# USB-C_Serial_16U2.net
KiCad netlist of a schematic drawn in Altium Designer
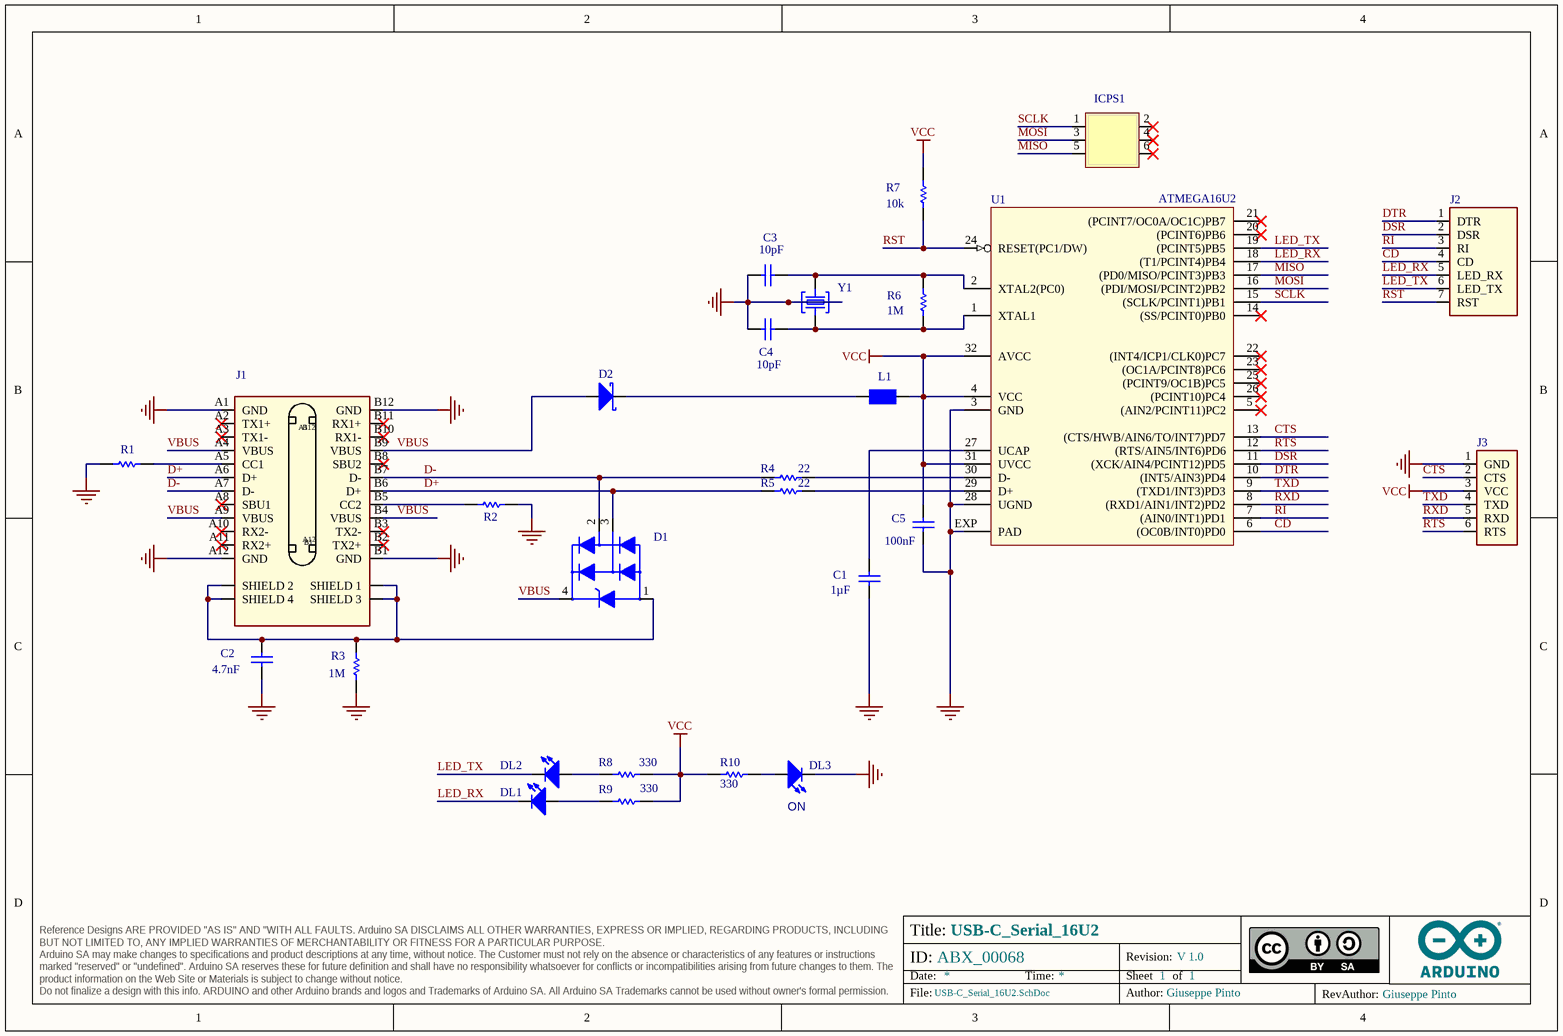
[diagram p0: USB-C_Serial_16U2.SchDoc]

(export (version "E")
  (design (tool "Eeschema 10.0.6"))
  (components
    (comp (ref "C1")
      (value "1µF")
      (footprint "CAP-0402")
      (description "CAP CHIP 0402 1uF 10V X5R 10%")
      (fields (field (name "VOLTAGE") "10V") (field (name "MANUFACTURER") "KEMET"))
      (libsource (lib "Clean") (part "CAP"))
    )
    (comp (ref "C2")
      (value "4.7nF")
      (footprint "CAP-0805")
      (description "CAP CHIP 0805 4.7nF 1000V X7R 10%")
      (fields (field (name "MANUFACTURER") "KEMET") (field (name "VOLTAGE") "1kV"))
      (libsource (lib "Clean") (part "CAP"))
    )
    (comp (ref "C3")
      (value "10pF")
      (footprint "CAP-0402")
      (description "CAP CHIP 0402 10pF 50V C0G 5%")
      (fields (field (name "MANUFACTURER") "KEMET") (field (name "PART NUMBER") "C0402H100J5GACTU"))
      (libsource (lib "Clean") (part "CAP"))
    )
    (comp (ref "C4")
      (value "10pF")
      (footprint "CAP-0402")
      (description "CAP CHIP 0402 10pF 50V C0G 5%")
      (fields (field (name "MANUFACTURER") "KEMET") (field (name "PART NUMBER") "C0402H100J5GACTU"))
      (libsource (lib "Clean") (part "CAP"))
    )
    (comp (ref "C5")
      (value "100nF")
      (footprint "CAP-0402")
      (description "CAP CHIP 0402 100nF 16V X7R 10%")
      (fields (field (name "VOLTAGE") "16V") (field (name "PART NUMBER") "C0402C104K4RACTU"))
      (libsource (lib "Clean") (part "C315C220J2G5TA"))
    )
    (comp (ref "D1")
      (value "PRTR5V0U2X,215")
      (footprint "SOT190P230X110-4N")
      (description "TVS ARRAY 4LIN.8kV 1pF SOT143B")
      (fields (field (name "MANUFACTURER") "Nexperia"))
      (libsource (lib "Clean") (part "PRTR5V0U2X,215"))
    )
    (comp (ref "D2")
      (value "PMEG6020AELRX")
      (footprint "SOD123-1")
      (description "DIODE SCHOTTKY SMD 2A 60V SOD123FL")
      (fields (field (name "MANUFACTURER") "Nexperia"))
      (libsource (lib "Clean") (part "PMEG6020AELRX"))
    )
    (comp (ref "DL1")
      (value "HSMD-C190")
      (footprint "LEDC1608X80N-AK")
      (description "LED SMD 0603 ORANGE604 8mcd DIFF.")
      (fields (field (name "MANUFACTURER") "Broadcom"))
      (libsource (lib "Clean") (part "LED"))
    )
    (comp (ref "DL2")
      (value "HSMD-C190")
      (footprint "LEDC1608X80N-AK")
      (description "LED SMD 0603 ORANGE604 8mcd DIFF.")
      (fields (field (name "MANUFACTURER") "Broadcom"))
      (libsource (lib "Clean") (part "LED"))
    )
    (comp (ref "DL3")
      (value "HSMG-C190")
      (footprint "LEDC1608X80N-AK")
      (description "LED SMD 0603 GREEN/568 15mcd 120^")
      (fields (field (name "MANUFACTURER") "Broadcom"))
      (libsource (lib "Clean") (part "LED"))
    )
    (comp (ref "ICPS1")
      (value "PINHD-2X03-SM-TP")
      (footprint "2X03-TP")
      (description "2X03 6 TEST POINTS")
      (libsource (lib "Clean") (part "Symbol"))
    )
    (comp (ref "J1")
      (value "12401598E4#2A")
      (footprint "12401598E4#2A")
      (description "CONN RCP USB3.1 TYPEC 24P SMD RA")
      (fields (field (name "MANUFACTURER") "Amphenol ICC (Commercial Products)"))
      (libsource (lib "Clean") (part "12401598E4#2A"))
    )
    (comp (ref "J2")
      (value "PH1-07-UA")
      (footprint "CONN STRIP 2.54 PIN HEADER DIP 180° 1x 7 PIN GOLD FLASH castelleted")
      (description "CONN STRIP 2.54 PIN HEADER DIP 180° 1x 7 PIN GOLD FLASH castelleted")
      (fields (field (name "MANUFACTURER") "4 UCONN"))
      (libsource (lib "Clean") (part "PH1-07-UA"))
    )
    (comp (ref "J3")
      (value "PH1-06-UA")
      (footprint "CONN STRP 2.54 PIN HEADER DIP 180° 1x X PIN GOLD FLASH")
      (description "CONN STRP 2.54 PIN HEADER DIP 180° 1x6 PIN GOLD FLASH castellated")
      (fields (field (name "MANUFACTURER") "4UCONN"))
      (libsource (lib "Clean") (part "PH1-06-UA"))
    )
    (comp (ref "L1")
      (value "BLM18PG471SN1D")
      (footprint "L-0603")
      (description "FERRITE SMD 0603 470R 1A 0.2R")
      (fields (field (name "TOLERANCE") "25%") (field (name "MANUFACTURER") "Murata"))
      (libsource (lib "Clean") (part "Ferrite"))
    )
    (comp (ref "R1")
      (value "RC0402FR-075K1L")
      (footprint "RES-0402")
      (description "RES CHIP 0402 5K1 1% 1/16W")
      (fields (field (name "TOLERANCE") "1%") (field (name "MANUFACTURER") "YAGEO"))
      (libsource (lib "Clean") (part "CRCW04025K10FKED"))
    )
    (comp (ref "R2")
      (value "RC0402FR-075K1L")
      (footprint "RES-0402")
      (description "RES CHIP 0402 5K1 1% 1/16W")
      (fields (field (name "TOLERANCE") "1%") (field (name "MANUFACTURER") "YAGEO"))
      (libsource (lib "Clean") (part "CRCW04025K10FKED"))
    )
    (comp (ref "R3")
      (value "1M")
      (footprint "RES-0402")
      (description "RES CHIP 0402 1M 1% 1/16W")
      (fields (field (name "POWER") "63mW") (field (name "TOLERANCE") "1%"))
      (libsource (lib "Clean") (part "RES"))
    )
    (comp (ref "R4")
      (value "22")
      (footprint "RES-0402")
      (description "RES CHIP 0402 22R 5% 1/16W")
      (fields (field (name "PART NUMBER") "CRCW040222R0JNEDC") (field (name "MANUFACTURER") "Vishay"))
      (libsource (lib "Clean") (part "RES"))
    )
    (comp (ref "R5")
      (value "22")
      (footprint "RES-0402")
      (description "RES CHIP 0402 22R 5% 1/16W")
      (fields (field (name "PART NUMBER") "CRCW040222R0JNEDC") (field (name "MANUFACTURER") "Vishay"))
      (libsource (lib "Clean") (part "RES"))
    )
    (comp (ref "R6")
      (value "1M")
      (footprint "RES-0402")
      (description "RES CHIP 0402 1M 1% 1/16W")
      (fields (field (name "POWER") "63mW") (field (name "TOLERANCE") "1%"))
      (libsource (lib "Clean") (part "RES"))
    )
    (comp (ref "R7")
      (value "10k")
      (footprint "RES-0402")
      (description "RES CHIP 0402 10K 1% 1/16W")
      (fields (field (name "MANUFACTURER") "Vishay") (field (name "POWER") "63mW"))
      (libsource (lib "Clean") (part "CRCW040256K2FKEDC"))
    )
    (comp (ref "R8")
      (value "330")
      (footprint "RES-0402")
      (description "RES CHIP 0402 330R 5% 1/16W")
      (fields (field (name "POWER") "63mW") (field (name "PART NUMBER") "CRCW0402330RJNED"))
      (libsource (lib "Clean") (part "CRCW040256K2FKEDC"))
    )
    (comp (ref "R9")
      (value "330")
      (footprint "RES-0402")
      (description "RES CHIP 0402 330R 5% 1/16W")
      (fields (field (name "POWER") "63mW") (field (name "PART NUMBER") "CRCW0402330RJNED"))
      (libsource (lib "Clean") (part "CRCW040256K2FKEDC"))
    )
    (comp (ref "R10")
      (value "330")
      (footprint "RES-0402")
      (description "RES CHIP 0402 330R 5% 1/16W")
      (fields (field (name "POWER") "63mW") (field (name "PART NUMBER") "CRCW0402330RJNED"))
      (libsource (lib "Clean") (part "RES"))
    )
    (comp (ref "U1")
      (value "ATMEGA16U2")
      (footprint "ATMEL_QFN32")
      (description "IC ATMEGA16U2")
      (fields (field (name "MANUFACTURER") "Microchip"))
      (libsource (lib "Clean") (part "ATMEGA16U2"))
    )
    (comp (ref "Y1")
      (value "FTX16.000M12SM3S-30/30")
      (footprint "CX3225SB16000D0GZJC1-Footprint-1")
      (description "CRYSTAL 16.0000MHZ 8PF SMD")
      (fields (field (name "MANUFACTURER") "Fronter Electronics"))
      (libsource (lib "Clean") (part "FTX16.000M12SM3S-30/30"))
    )
  )
  (nets
    (net (code "1") (name "/CD") (class "Default")
      (node (ref "J2") (pin "4") (pinfunction "CD_4") (pintype "passive"))
      (node (ref "U1") (pin "6") (pinfunction "(OC0B/INT0)PD0_6") (pintype "passive"))
    )
    (net (code "2") (name "/CTS") (class "Default")
      (node (ref "J3") (pin "2") (pinfunction "CTS_2") (pintype "passive"))
      (node (ref "U1") (pin "13") (pinfunction "(CTS/HWB/AIN6/TO/INT7)PD7_13") (pintype "passive"))
    )
    (net (code "3") (name "/D+") (class "Default")
      (node (ref "D1") (pin "3") (pinfunction "3_3") (pintype "passive"))
      (node (ref "J1") (pin "A6") (pinfunction "D+_A6") (pintype "passive"))
      (node (ref "J1") (pin "B6") (pinfunction "D+_B6") (pintype "passive"))
      (node (ref "R5") (pin "1") (pinfunction "1_1") (pintype "passive"))
    )
    (net (code "4") (name "/D-") (class "Default")
      (node (ref "D1") (pin "2") (pinfunction "2_2") (pintype "passive"))
      (node (ref "J1") (pin "A7") (pinfunction "D-_A7") (pintype "passive"))
      (node (ref "J1") (pin "B7") (pinfunction "D-_B7") (pintype "passive"))
      (node (ref "R4") (pin "1") (pinfunction "1_1") (pintype "passive"))
    )
    (net (code "5") (name "/DSR") (class "Default")
      (node (ref "J2") (pin "2") (pinfunction "DSR_2") (pintype "passive"))
      (node (ref "U1") (pin "11") (pinfunction "(XCK/AIN4/PCINT12)PD5_11") (pintype "passive"))
    )
    (net (code "6") (name "/DTR") (class "Default")
      (node (ref "J2") (pin "1") (pinfunction "DTR_1") (pintype "passive"))
      (node (ref "U1") (pin "10") (pinfunction "(INT5/AIN3)PD4_10") (pintype "passive"))
    )
    (net (code "7") (name "/LED_RX") (class "Default")
      (node (ref "DL1") (pin "C") (pinfunction "C_C") (pintype "passive"))
      (node (ref "J2") (pin "5") (pinfunction "LED_RX_5") (pintype "passive"))
      (node (ref "U1") (pin "18") (pinfunction "(T1/PCINT4)PB4_18") (pintype "passive"))
    )
    (net (code "8") (name "/LED_TX") (class "Default")
      (node (ref "DL2") (pin "C") (pinfunction "C_C") (pintype "passive"))
      (node (ref "J2") (pin "6") (pinfunction "LED_TX_6") (pintype "passive"))
      (node (ref "U1") (pin "19") (pinfunction "(PCINT5)PB5_19") (pintype "passive"))
    )
    (net (code "9") (name "/MISO") (class "Default")
      (node (ref "ICPS1") (pin "5") (pinfunction "5_5") (pintype "passive"))
      (node (ref "U1") (pin "17") (pinfunction "(PD0/MISO/PCINT3)PB3_17") (pintype "passive"))
    )
    (net (code "10") (name "/MOSI") (class "Default")
      (node (ref "ICPS1") (pin "3") (pinfunction "3_3") (pintype "passive"))
      (node (ref "U1") (pin "16") (pinfunction "(PDI/MOSI/PCINT2)PB2_16") (pintype "passive"))
    )
    (net (code "11") (name "/RI") (class "Default")
      (node (ref "J2") (pin "3") (pinfunction "RI_3") (pintype "passive"))
      (node (ref "U1") (pin "7") (pinfunction "(AIN0/INT1)PD1_7") (pintype "passive"))
    )
    (net (code "12") (name "/RST") (class "Default")
      (node (ref "J2") (pin "7") (pinfunction "RST_7") (pintype "passive"))
      (node (ref "R7") (pin "1") (pinfunction "1_1") (pintype "passive"))
      (node (ref "U1") (pin "24") (pinfunction "RESET(PC1/DW)_24") (pintype "input"))
    )
    (net (code "13") (name "/RTS") (class "Default")
      (node (ref "J3") (pin "6") (pinfunction "RTS_6") (pintype "passive"))
      (node (ref "U1") (pin "12") (pinfunction "(RTS/AIN5/INT6)PD6_12") (pintype "passive"))
    )
    (net (code "14") (name "/RXD") (class "Default")
      (node (ref "J3") (pin "5") (pinfunction "RXD_5") (pintype "passive"))
      (node (ref "U1") (pin "8") (pinfunction "(RXD1/AIN1/INT2)PD2_8") (pintype "passive"))
    )
    (net (code "15") (name "/SCLK") (class "Default")
      (node (ref "ICPS1") (pin "1") (pinfunction "1_1") (pintype "passive"))
      (node (ref "U1") (pin "15") (pinfunction "(SCLK/PCINT1)PB1_15") (pintype "passive"))
    )
    (net (code "16") (name "/TXD") (class "Default")
      (node (ref "J3") (pin "4") (pinfunction "TXD_4") (pintype "passive"))
      (node (ref "U1") (pin "9") (pinfunction "(TXD1/INT3)PD3_9") (pintype "passive"))
    )
    (net (code "17") (name "/VBUS") (class "Default")
      (node (ref "D1") (pin "4") (pinfunction "4_4") (pintype "passive"))
      (node (ref "D2") (pin "A") (pinfunction "A_A") (pintype "passive"))
      (node (ref "J1") (pin "A4") (pinfunction "VBUS_A4") (pintype "passive"))
      (node (ref "J1") (pin "A9") (pinfunction "VBUS_A9") (pintype "passive"))
      (node (ref "J1") (pin "B4") (pinfunction "VBUS_B4") (pintype "passive"))
      (node (ref "J1") (pin "B9") (pinfunction "VBUS_B9") (pintype "passive"))
    )
    (net (code "18") (name "GND") (class "Default")
      (node (ref "C1") (pin "2") (pinfunction "2_2") (pintype "passive"))
      (node (ref "C2") (pin "1") (pinfunction "1_1") (pintype "passive"))
      (node (ref "C3") (pin "1") (pinfunction "1_1") (pintype "passive"))
      (node (ref "C4") (pin "1") (pinfunction "1_1") (pintype "passive"))
      (node (ref "C5") (pin "1") (pinfunction "1_1") (pintype "passive"))
      (node (ref "DL3") (pin "C") (pinfunction "C_C") (pintype "passive"))
      (node (ref "J1") (pin "A1") (pinfunction "GND_A1") (pintype "passive"))
      (node (ref "J1") (pin "A12") (pinfunction "GND_A12") (pintype "passive"))
      (node (ref "J1") (pin "B1") (pinfunction "GND_B1") (pintype "passive"))
      (node (ref "J1") (pin "B12") (pinfunction "GND_B12") (pintype "passive"))
      (node (ref "J3") (pin "1") (pinfunction "GND_1") (pintype "passive"))
      (node (ref "R1") (pin "1") (pinfunction "1_1") (pintype "passive"))
      (node (ref "R2") (pin "2") (pinfunction "2_2") (pintype "passive"))
      (node (ref "R3") (pin "1") (pinfunction "1_1") (pintype "passive"))
      (node (ref "U1") (pin "28") (pinfunction "UGND_28") (pintype "power_in"))
      (node (ref "U1") (pin "3") (pinfunction "GND_3") (pintype "power_in"))
      (node (ref "U1") (pin "EXP") (pinfunction "PAD_EXP") (pintype "power_in"))
      (node (ref "Y1") (pin "2") (pinfunction "2_2") (pintype "passive"))
      (node (ref "Y1") (pin "4") (pinfunction "4_4") (pintype "passive"))
    )
    (net (code "19") (name "Net-(C2-Pad2)") (class "Default")
      (node (ref "C2") (pin "2") (pinfunction "2_2") (pintype "passive"))
      (node (ref "D1") (pin "1") (pinfunction "1_1") (pintype "passive"))
      (node (ref "J1") (pin "SHIELD_1") (pinfunction "SHIELD_1_SHIELD_1") (pintype "passive"))
      (node (ref "J1") (pin "SHIELD_2") (pinfunction "SHIELD_2_SHIELD_2") (pintype "passive"))
      (node (ref "J1") (pin "SHIELD_3") (pinfunction "SHIELD_3_SHIELD_3") (pintype "passive"))
      (node (ref "J1") (pin "SHIELD_4") (pinfunction "SHIELD_4_SHIELD_4") (pintype "passive"))
      (node (ref "R3") (pin "2") (pinfunction "2_2") (pintype "passive"))
    )
    (net (code "20") (name "Net-(D2-PadC)") (class "Default")
      (node (ref "D2") (pin "C") (pinfunction "C_C") (pintype "passive"))
      (node (ref "L1") (pin "1") (pinfunction "1_1") (pintype "passive"))
    )
    (net (code "21") (name "Net-(DL1-PadA)") (class "Default")
      (node (ref "DL1") (pin "A") (pinfunction "A_A") (pintype "passive"))
      (node (ref "R9") (pin "1") (pinfunction "1_1") (pintype "passive"))
    )
    (net (code "22") (name "Net-(DL2-PadA)") (class "Default")
      (node (ref "DL2") (pin "A") (pinfunction "A_A") (pintype "passive"))
      (node (ref "R8") (pin "2") (pinfunction "2_2") (pintype "passive"))
    )
    (net (code "23") (name "Net-(DL3-PadA)") (class "Default")
      (node (ref "DL3") (pin "A") (pinfunction "A_A") (pintype "passive"))
      (node (ref "R10") (pin "1") (pinfunction "1_1") (pintype "passive"))
    )
    (net (code "24") (name "Net-(J1-CC1)") (class "Default")
      (node (ref "J1") (pin "A5") (pinfunction "CC1_A5") (pintype "passive"))
      (node (ref "R1") (pin "2") (pinfunction "2_2") (pintype "passive"))
    )
    (net (code "25") (name "Net-(J1-CC2)") (class "Default")
      (node (ref "J1") (pin "B5") (pinfunction "CC2_B5") (pintype "passive"))
      (node (ref "R2") (pin "1") (pinfunction "1_1") (pintype "passive"))
    )
    (net (code "26") (name "Net-(U1-D+)") (class "Default")
      (node (ref "R5") (pin "2") (pinfunction "2_2") (pintype "passive"))
      (node (ref "U1") (pin "29") (pinfunction "D+_29") (pintype "passive"))
    )
    (net (code "27") (name "Net-(U1-D-)") (class "Default")
      (node (ref "R4") (pin "2") (pinfunction "2_2") (pintype "passive"))
      (node (ref "U1") (pin "30") (pinfunction "D-_30") (pintype "passive"))
    )
    (net (code "28") (name "Net-(U1-UCAP)") (class "Default")
      (node (ref "C1") (pin "1") (pinfunction "1_1") (pintype "passive"))
      (node (ref "U1") (pin "27") (pinfunction "UCAP_27") (pintype "passive"))
    )
    (net (code "29") (name "Net-(U1-XTAL1)") (class "Default")
      (node (ref "C4") (pin "2") (pinfunction "2_2") (pintype "passive"))
      (node (ref "R6") (pin "1") (pinfunction "1_1") (pintype "passive"))
      (node (ref "U1") (pin "1") (pinfunction "XTAL1_1") (pintype "passive"))
      (node (ref "Y1") (pin "1") (pinfunction "1_1") (pintype "passive"))
    )
    (net (code "30") (name "Net-(U1-XTAL2(PC0))") (class "Default")
      (node (ref "C3") (pin "2") (pinfunction "2_2") (pintype "passive"))
      (node (ref "R6") (pin "2") (pinfunction "2_2") (pintype "passive"))
      (node (ref "U1") (pin "2") (pinfunction "XTAL2(PC0)_2") (pintype "passive"))
      (node (ref "Y1") (pin "3") (pinfunction "3_3") (pintype "passive"))
    )
    (net (code "31") (name "VCC") (class "Default")
      (node (ref "C5") (pin "2") (pinfunction "2_2") (pintype "passive"))
      (node (ref "J3") (pin "3") (pinfunction "VCC_3") (pintype "passive"))
      (node (ref "L1") (pin "2") (pinfunction "2_2") (pintype "passive"))
      (node (ref "R10") (pin "2") (pinfunction "2_2") (pintype "passive"))
      (node (ref "R7") (pin "2") (pinfunction "2_2") (pintype "passive"))
      (node (ref "R8") (pin "1") (pinfunction "1_1") (pintype "passive"))
      (node (ref "R9") (pin "2") (pinfunction "2_2") (pintype "passive"))
      (node (ref "U1") (pin "31") (pinfunction "UVCC_31") (pintype "power_in"))
      (node (ref "U1") (pin "32") (pinfunction "AVCC_32") (pintype "power_in"))
      (node (ref "U1") (pin "4") (pinfunction "VCC_4") (pintype "power_in"))
    )
    (net (code "32") (name "unconnected-(ICPS1-Pad2)") (class "Default")
      (node (ref "ICPS1") (pin "2") (pinfunction "2_2") (pintype "passive+no_connect"))
    )
    (net (code "33") (name "unconnected-(ICPS1-Pad4)") (class "Default")
      (node (ref "ICPS1") (pin "4") (pinfunction "4_4") (pintype "passive+no_connect"))
    )
    (net (code "34") (name "unconnected-(ICPS1-Pad6)") (class "Default")
      (node (ref "ICPS1") (pin "6") (pinfunction "6_6") (pintype "passive+no_connect"))
    )
    (net (code "35") (name "unconnected-(J1-RX1+-PadB11)") (class "Default")
      (node (ref "J1") (pin "B11") (pinfunction "RX1+_B11") (pintype "passive+no_connect"))
    )
    (net (code "36") (name "unconnected-(J1-RX1--PadB10)") (class "Default")
      (node (ref "J1") (pin "B10") (pinfunction "RX1-_B10") (pintype "passive+no_connect"))
    )
    (net (code "37") (name "unconnected-(J1-RX2+-PadA11)") (class "Default")
      (node (ref "J1") (pin "A11") (pinfunction "RX2+_A11") (pintype "passive+no_connect"))
    )
    (net (code "38") (name "unconnected-(J1-RX2--PadA10)") (class "Default")
      (node (ref "J1") (pin "A10") (pinfunction "RX2-_A10") (pintype "passive+no_connect"))
    )
    (net (code "39") (name "unconnected-(J1-SBU1-PadA8)") (class "Default")
      (node (ref "J1") (pin "A8") (pinfunction "SBU1_A8") (pintype "passive+no_connect"))
    )
    (net (code "40") (name "unconnected-(J1-SBU2-PadB8)") (class "Default")
      (node (ref "J1") (pin "B8") (pinfunction "SBU2_B8") (pintype "passive+no_connect"))
    )
    (net (code "41") (name "unconnected-(J1-TX1+-PadA2)") (class "Default")
      (node (ref "J1") (pin "A2") (pinfunction "TX1+_A2") (pintype "passive+no_connect"))
    )
    (net (code "42") (name "unconnected-(J1-TX1--PadA3)") (class "Default")
      (node (ref "J1") (pin "A3") (pinfunction "TX1-_A3") (pintype "passive+no_connect"))
    )
    (net (code "43") (name "unconnected-(J1-TX2+-PadB2)") (class "Default")
      (node (ref "J1") (pin "B2") (pinfunction "TX2+_B2") (pintype "passive+no_connect"))
    )
    (net (code "44") (name "unconnected-(J1-TX2--PadB3)") (class "Default")
      (node (ref "J1") (pin "B3") (pinfunction "TX2-_B3") (pintype "passive+no_connect"))
    )
    (net (code "45") (name "unconnected-(U1-(AIN2{slash}PCINT11)PC2-Pad5)") (class "Default")
      (node (ref "U1") (pin "5") (pinfunction "(AIN2/PCINT11)PC2_5") (pintype "passive+no_connect"))
    )
    (net (code "46") (name "unconnected-(U1-(INT4{slash}ICP1{slash}CLK0)PC7-Pad22)") (class "Default")
      (node (ref "U1") (pin "22") (pinfunction "(INT4/ICP1/CLK0)PC7_22") (pintype "passive+no_connect"))
    )
    (net (code "47") (name "unconnected-(U1-(OC1A{slash}PCINT8)PC6-Pad23)") (class "Default")
      (node (ref "U1") (pin "23") (pinfunction "(OC1A/PCINT8)PC6_23") (pintype "passive+no_connect"))
    )
    (net (code "48") (name "unconnected-(U1-(PCINT6)PB6-Pad20)") (class "Default")
      (node (ref "U1") (pin "20") (pinfunction "(PCINT6)PB6_20") (pintype "passive+no_connect"))
    )
    (net (code "49") (name "unconnected-(U1-(PCINT7{slash}OC0A{slash}OC1C)PB7-Pad21)") (class "Default")
      (node (ref "U1") (pin "21") (pinfunction "(PCINT7/OC0A/OC1C)PB7_21") (pintype "passive+no_connect"))
    )
    (net (code "50") (name "unconnected-(U1-(PCINT9{slash}OC1B)PC5-Pad25)") (class "Default")
      (node (ref "U1") (pin "25") (pinfunction "(PCINT9/OC1B)PC5_25") (pintype "passive+no_connect"))
    )
    (net (code "51") (name "unconnected-(U1-(PCINT10)PC4-Pad26)") (class "Default")
      (node (ref "U1") (pin "26") (pinfunction "(PCINT10)PC4_26") (pintype "passive+no_connect"))
    )
    (net (code "52") (name "unconnected-(U1-(SS{slash}PCINT0)PB0-Pad14)") (class "Default")
      (node (ref "U1") (pin "14") (pinfunction "(SS/PCINT0)PB0_14") (pintype "passive+no_connect"))
    )
  )
)
